# Sheet1.net
KiCad netlist of a schematic drawn in Altium Designer
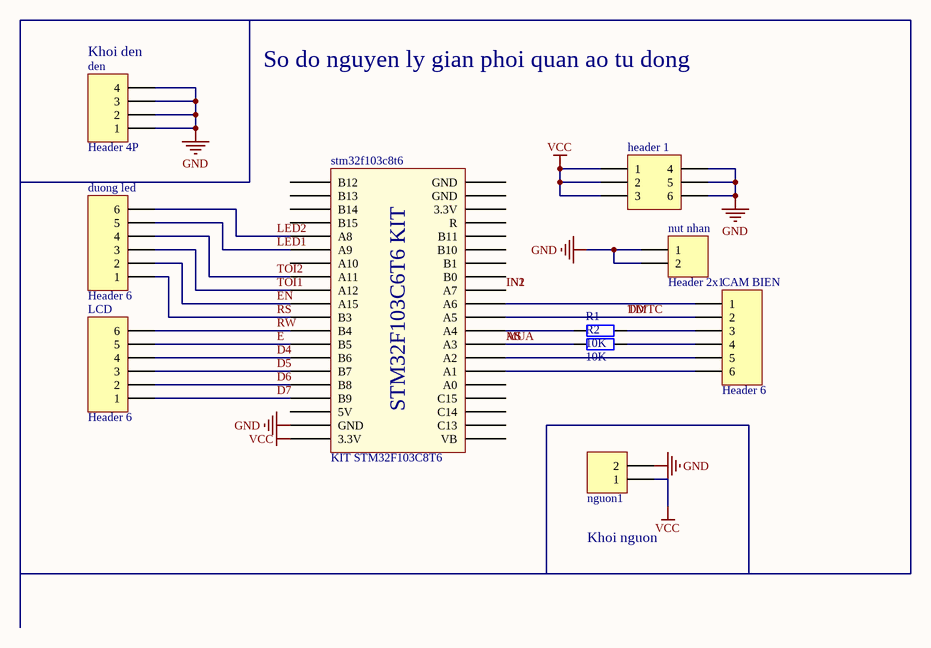
[diagram p0: Sheet1.SchDoc]

(export (version "E")
  (design (tool "Eeschema 10.0.6"))
  (components
    (comp (ref "CAM BIEN")
      (value "Header 6")
      (footprint "HDR1X6")
      (description "Header, 6-Pin")
      (libsource (lib "") (part "Header 6_1"))
    )
    (comp (ref "den")
      (value "Header 4P")
      (footprint "HDR1X4")
      (description "Header, 4 Pin Pitch 2.54mm")
      (fields (field (name "MPN") "S1012EC-40-ND"))
      (libsource (lib "BYTECH_HW_LIB_2019 (1)") (part "Header 4x1"))
    )
    (comp (ref "duong led")
      (value "Header 6")
      (footprint "HDR1X6")
      (description "Header, 6-Pin")
      (libsource (lib "BYTECH_HW_LIB_2019 (1)") (part "Header 6"))
    )
    (comp (ref "header 1")
      (value "Header 3X2A")
      (footprint "HDR2X3_CEN")
      (description "Header, 3-Pin, Dual row")
      (libsource (lib "BYTECH_HW_LIB_2019 (1)") (part "Header 3X2A"))
    )
    (comp (ref "LCD")
      (value "Header 6")
      (footprint "HDR1X6")
      (description "Header, 6-Pin")
      (libsource (lib "BYTECH_HW_LIB_2019 (1)") (part "Header 6"))
    )
    (comp (ref "nguon1")
      (value "Header 2_1")
      (footprint "HED2")
      (description "Header, 2-Pin")
      (fields (field (name "MANUFACTURER") "Generic Components"))
      (libsource (lib "Thuvien3D") (part "Header 2_1"))
    )
    (comp (ref "nut nhan")
      (value "Header 2x1")
      (footprint "HDR1X2")
      (description "Header, 2-Pin, pitch 2.54mm")
      (libsource (lib "BYTECH_HW_LIB_2019 (1)") (part "Header 2x1"))
    )
    (comp (ref "R1")
      (value "10K")
      (footprint "R1/4W")
      (description "Resistor 1/4W")
      (libsource (lib "Thuvien3D") (part "R1/4W"))
    )
    (comp (ref "R2")
      (value "10K")
      (footprint "R1/4W")
      (description "Resistor 1/4W")
      (libsource (lib "Thuvien3D") (part "R1/4W"))
    )
    (comp (ref "stm32f103c8t6")
      (value "KIT STM32F103C8T6")
      (footprint "STM32F103 KIT")
      (description "KIT STM32F103C8T6 Bluepill")
      (libsource (lib "Altium_Lib_by_KhueNguyenCreator") (part "STM32f103 Bluepill"))
    )
  )
  (nets
    (net (code "1") (name "/AS") (class "Default")
      (node (ref "R2") (pin "1") (pinfunction "1_1") (pintype "passive"))
      (node (ref "stm32f103c8t6") (pin "28") (pinfunction "A3_28") (pintype "passive"))
    )
    (net (code "2") (name "/D4") (class "Default")
      (node (ref "LCD") (pin "4") (pinfunction "4_4") (pintype "passive"))
      (node (ref "stm32f103c8t6") (pin "14") (pinfunction "B6_14") (pintype "passive"))
    )
    (net (code "3") (name "/D5") (class "Default")
      (node (ref "LCD") (pin "3") (pinfunction "3_3") (pintype "passive"))
      (node (ref "stm32f103c8t6") (pin "15") (pinfunction "B7_15") (pintype "passive"))
    )
    (net (code "4") (name "/D6") (class "Default")
      (node (ref "LCD") (pin "2") (pinfunction "2_2") (pintype "passive"))
      (node (ref "stm32f103c8t6") (pin "16") (pinfunction "B8_16") (pintype "passive"))
    )
    (net (code "5") (name "/D7") (class "Default")
      (node (ref "LCD") (pin "1") (pinfunction "1_1") (pintype "passive"))
      (node (ref "stm32f103c8t6") (pin "17") (pinfunction "B9_17") (pintype "passive"))
    )
    (net (code "6") (name "/DM") (class "Default")
      (node (ref "CAM BIEN") (pin "2") (pinfunction "2_2") (pintype "passive"))
      (node (ref "stm32f103c8t6") (pin "30") (pinfunction "A5_30") (pintype "passive"))
    )
    (net (code "7") (name "/E") (class "Default")
      (node (ref "LCD") (pin "5") (pinfunction "5_5") (pintype "passive"))
      (node (ref "stm32f103c8t6") (pin "13") (pinfunction "B5_13") (pintype "passive"))
    )
    (net (code "8") (name "/EN") (class "Default")
      (node (ref "duong led") (pin "2") (pinfunction "2_2") (pintype "passive"))
      (node (ref "stm32f103c8t6") (pin "10") (pinfunction "A15_10") (pintype "passive"))
    )
    (net (code "9") (name "/IN1") (class "Default")
      (node (ref "stm32f103c8t6") (pin "32") (pinfunction "A7_32") (pintype "passive"))
    )
    (net (code "10") (name "/LED1") (class "Default")
      (node (ref "duong led") (pin "5") (pinfunction "5_5") (pintype "passive"))
      (node (ref "stm32f103c8t6") (pin "6") (pinfunction "A9_6") (pintype "passive"))
    )
    (net (code "11") (name "/LED2") (class "Default")
      (node (ref "duong led") (pin "6") (pinfunction "6_6") (pintype "passive"))
      (node (ref "stm32f103c8t6") (pin "5") (pinfunction "A8_5") (pintype "passive"))
    )
    (net (code "12") (name "/RS") (class "Default")
      (node (ref "duong led") (pin "1") (pinfunction "1_1") (pintype "passive"))
      (node (ref "stm32f103c8t6") (pin "11") (pinfunction "B3_11") (pintype "passive"))
    )
    (net (code "13") (name "/RW") (class "Default")
      (node (ref "LCD") (pin "6") (pinfunction "6_6") (pintype "passive"))
      (node (ref "stm32f103c8t6") (pin "12") (pinfunction "B4_12") (pintype "passive"))
    )
    (net (code "14") (name "/TOI1") (class "Default")
      (node (ref "duong led") (pin "3") (pinfunction "3_3") (pintype "passive"))
      (node (ref "stm32f103c8t6") (pin "9") (pinfunction "A12_9") (pintype "passive"))
    )
    (net (code "15") (name "/TOI2") (class "Default")
      (node (ref "duong led") (pin "4") (pinfunction "4_4") (pintype "passive"))
      (node (ref "stm32f103c8t6") (pin "8") (pinfunction "A11_8") (pintype "passive"))
    )
    (net (code "16") (name "GND") (class "Default")
      (node (ref "den") (pin "1") (pinfunction "1_1") (pintype "passive"))
      (node (ref "den") (pin "2") (pinfunction "2_2") (pintype "passive"))
      (node (ref "den") (pin "3") (pinfunction "3_3") (pintype "passive"))
      (node (ref "den") (pin "4") (pinfunction "4_4") (pintype "passive"))
      (node (ref "header 1") (pin "4") (pinfunction "4_4") (pintype "passive"))
      (node (ref "header 1") (pin "5") (pinfunction "5_5") (pintype "passive"))
      (node (ref "header 1") (pin "6") (pinfunction "6_6") (pintype "passive"))
      (node (ref "nguon1") (pin "2") (pinfunction "2_2") (pintype "passive"))
      (node (ref "nut nhan") (pin "1") (pinfunction "1_1") (pintype "passive"))
      (node (ref "nut nhan") (pin "2") (pinfunction "2_2") (pintype "passive"))
      (node (ref "stm32f103c8t6") (pin "19") (pinfunction "GND_19") (pintype "passive"))
    )
    (net (code "17") (name "Net-(CAM BIEN-Pad3)") (class "Default")
      (node (ref "CAM BIEN") (pin "3") (pinfunction "3_3") (pintype "passive"))
      (node (ref "R1") (pin "2") (pinfunction "2_2") (pintype "passive"))
    )
    (net (code "18") (name "Net-(CAM BIEN-Pad4)") (class "Default")
      (node (ref "CAM BIEN") (pin "4") (pinfunction "4_4") (pintype "passive"))
      (node (ref "R2") (pin "2") (pinfunction "2_2") (pintype "passive"))
    )
    (net (code "19") (name "Net-(stm32f103c8t6-A1)") (class "Default")
      (node (ref "CAM BIEN") (pin "6") (pinfunction "6_6") (pintype "passive"))
      (node (ref "stm32f103c8t6") (pin "26") (pinfunction "A1_26") (pintype "passive"))
    )
    (net (code "20") (name "Net-(stm32f103c8t6-A2)") (class "Default")
      (node (ref "CAM BIEN") (pin "5") (pinfunction "5_5") (pintype "passive"))
      (node (ref "stm32f103c8t6") (pin "27") (pinfunction "A2_27") (pintype "passive"))
    )
    (net (code "21") (name "Net-(stm32f103c8t6-A4)") (class "Default")
      (node (ref "R1") (pin "1") (pinfunction "1_1") (pintype "passive"))
      (node (ref "stm32f103c8t6") (pin "29") (pinfunction "A4_29") (pintype "passive"))
    )
    (net (code "22") (name "Net-(stm32f103c8t6-A6)") (class "Default")
      (node (ref "CAM BIEN") (pin "1") (pinfunction "1_1") (pintype "passive"))
      (node (ref "stm32f103c8t6") (pin "31") (pinfunction "A6_31") (pintype "passive"))
    )
    (net (code "23") (name "VCC") (class "Default")
      (node (ref "header 1") (pin "1") (pinfunction "1_1") (pintype "passive"))
      (node (ref "header 1") (pin "2") (pinfunction "2_2") (pintype "passive"))
      (node (ref "header 1") (pin "3") (pinfunction "3_3") (pintype "passive"))
      (node (ref "nguon1") (pin "1") (pinfunction "1_1") (pintype "passive"))
      (node (ref "stm32f103c8t6") (pin "20") (pinfunction "3.3V_20") (pintype "passive"))
    )
    (net (code "24") (name "unconnected-(stm32f103c8t6-3.3V-Pad38)") (class "Default")
      (node (ref "stm32f103c8t6") (pin "38") (pinfunction "3.3V_38") (pintype "passive"))
    )
    (net (code "25") (name "unconnected-(stm32f103c8t6-5V-Pad18)") (class "Default")
      (node (ref "stm32f103c8t6") (pin "18") (pinfunction "5V_18") (pintype "passive"))
    )
    (net (code "26") (name "unconnected-(stm32f103c8t6-A0-Pad25)") (class "Default")
      (node (ref "stm32f103c8t6") (pin "25") (pinfunction "A0_25") (pintype "passive"))
    )
    (net (code "27") (name "unconnected-(stm32f103c8t6-A10-Pad7)") (class "Default")
      (node (ref "stm32f103c8t6") (pin "7") (pinfunction "A10_7") (pintype "passive"))
    )
    (net (code "28") (name "unconnected-(stm32f103c8t6-B0-Pad33)") (class "Default")
      (node (ref "stm32f103c8t6") (pin "33") (pinfunction "B0_33") (pintype "passive"))
    )
    (net (code "29") (name "unconnected-(stm32f103c8t6-B1-Pad34)") (class "Default")
      (node (ref "stm32f103c8t6") (pin "34") (pinfunction "B1_34") (pintype "passive"))
    )
    (net (code "30") (name "unconnected-(stm32f103c8t6-B10-Pad35)") (class "Default")
      (node (ref "stm32f103c8t6") (pin "35") (pinfunction "B10_35") (pintype "passive"))
    )
    (net (code "31") (name "unconnected-(stm32f103c8t6-B11-Pad36)") (class "Default")
      (node (ref "stm32f103c8t6") (pin "36") (pinfunction "B11_36") (pintype "passive"))
    )
    (net (code "32") (name "unconnected-(stm32f103c8t6-B12-Pad1)") (class "Default")
      (node (ref "stm32f103c8t6") (pin "1") (pinfunction "B12_1") (pintype "passive"))
    )
    (net (code "33") (name "unconnected-(stm32f103c8t6-B13-Pad2)") (class "Default")
      (node (ref "stm32f103c8t6") (pin "2") (pinfunction "B13_2") (pintype "passive"))
    )
    (net (code "34") (name "unconnected-(stm32f103c8t6-B14-Pad3)") (class "Default")
      (node (ref "stm32f103c8t6") (pin "3") (pinfunction "B14_3") (pintype "passive"))
    )
    (net (code "35") (name "unconnected-(stm32f103c8t6-B15-Pad4)") (class "Default")
      (node (ref "stm32f103c8t6") (pin "4") (pinfunction "B15_4") (pintype "passive"))
    )
    (net (code "36") (name "unconnected-(stm32f103c8t6-C13-Pad22)") (class "Default")
      (node (ref "stm32f103c8t6") (pin "22") (pinfunction "C13_22") (pintype "passive"))
    )
    (net (code "37") (name "unconnected-(stm32f103c8t6-C14-Pad23)") (class "Default")
      (node (ref "stm32f103c8t6") (pin "23") (pinfunction "C14_23") (pintype "passive"))
    )
    (net (code "38") (name "unconnected-(stm32f103c8t6-C15-Pad24)") (class "Default")
      (node (ref "stm32f103c8t6") (pin "24") (pinfunction "C15_24") (pintype "passive"))
    )
    (net (code "39") (name "unconnected-(stm32f103c8t6-GND-Pad39)") (class "Default")
      (node (ref "stm32f103c8t6") (pin "39") (pinfunction "GND_39") (pintype "passive"))
    )
    (net (code "40") (name "unconnected-(stm32f103c8t6-GND-Pad40)") (class "Default")
      (node (ref "stm32f103c8t6") (pin "40") (pinfunction "GND_40") (pintype "passive"))
    )
    (net (code "41") (name "unconnected-(stm32f103c8t6-R-Pad37)") (class "Default")
      (node (ref "stm32f103c8t6") (pin "37") (pinfunction "R_37") (pintype "passive"))
    )
    (net (code "42") (name "unconnected-(stm32f103c8t6-VB-Pad21)") (class "Default")
      (node (ref "stm32f103c8t6") (pin "21") (pinfunction "VB_21") (pintype "passive"))
    )
  )
)
